# circuit.net
KiCad netlist of a schematic drawn in EAGLE
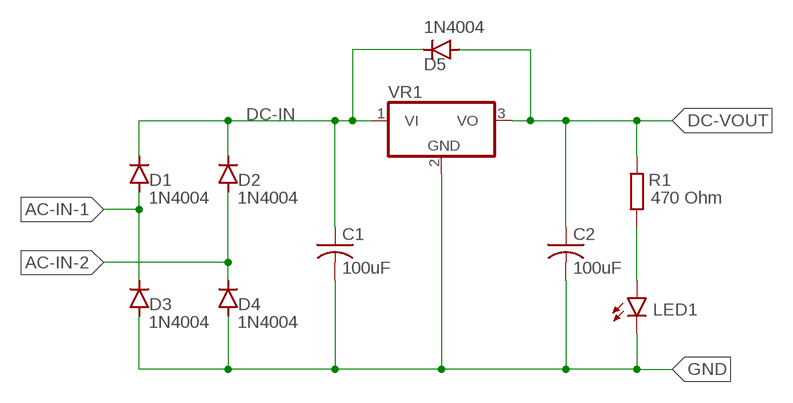
[diagram p0: schematic, sheet 1]

(export (version "E")
  (design (tool "Eeschema 10.0.6"))
  (components
    (comp (ref "C1")
      (value "100uF")
      (footprint "eagle-import:C050-045X075")
      (libsource (lib "eagle-import") (part "C-US050-045X075"))
    )
    (comp (ref "C2")
      (value "100uF")
      (footprint "eagle-import:C050-045X075")
      (libsource (lib "eagle-import") (part "C-US050-045X075"))
    )
    (comp (ref "D1")
      (value "1N4004")
      (footprint "eagle-import:DO41-10")
      (libsource (lib "eagle-import") (part "1N4004"))
    )
    (comp (ref "D2")
      (value "1N4004")
      (footprint "eagle-import:DO41-10")
      (libsource (lib "eagle-import") (part "1N4004"))
    )
    (comp (ref "D3")
      (value "1N4004")
      (footprint "eagle-import:DO41-10")
      (libsource (lib "eagle-import") (part "1N4004"))
    )
    (comp (ref "D4")
      (value "1N4004")
      (footprint "eagle-import:DO41-10")
      (libsource (lib "eagle-import") (part "1N4004"))
    )
    (comp (ref "D5")
      (value "1N4004")
      (footprint "eagle-import:DO41-10")
      (libsource (lib "eagle-import") (part "1N4004"))
    )
    (comp (ref "LED1")
      (value "LED5MM")
      (footprint "eagle-import:LED5MM")
      (libsource (lib "eagle-import") (part "LED5MM"))
    )
    (comp (ref "R1")
      (value "470 Ohm")
      (footprint "eagle-import:0207_10")
      (libsource (lib "eagle-import") (part "R-EU_0207/10"))
    )
    (comp (ref "VR1")
      (value "788TV")
      (footprint "eagle-import:TO220V")
      (libsource (lib "eagle-import") (part "78TV8"))
    )
  )
  (nets
    (net (code "1") (name "/DC-IN") (class "Default")
      (node (ref "C1") (pin "1") (pinfunction "1_1") (pintype "passive"))
      (node (ref "D1") (pin "C") (pinfunction "C_C") (pintype "passive"))
      (node (ref "D2") (pin "C") (pinfunction "C_C") (pintype "passive"))
      (node (ref "D5") (pin "C") (pinfunction "C_C") (pintype "passive"))
      (node (ref "VR1") (pin "1") (pinfunction "VI_1") (pintype "input"))
    )
    (net (code "2") (name "AC-IN-1") (class "Default")
      (node (ref "D1") (pin "A") (pinfunction "A_A") (pintype "passive"))
      (node (ref "D3") (pin "C") (pinfunction "C_C") (pintype "passive"))
    )
    (net (code "3") (name "AC-IN-2") (class "Default")
      (node (ref "D2") (pin "A") (pinfunction "A_A") (pintype "passive"))
      (node (ref "D4") (pin "C") (pinfunction "C_C") (pintype "passive"))
    )
    (net (code "4") (name "DC-VOUT") (class "Default")
      (node (ref "C2") (pin "1") (pinfunction "1_1") (pintype "passive"))
      (node (ref "D5") (pin "A") (pinfunction "A_A") (pintype "passive"))
      (node (ref "R1") (pin "2") (pinfunction "2_2") (pintype "passive"))
      (node (ref "VR1") (pin "3") (pinfunction "VO_3") (pintype "passive"))
    )
    (net (code "5") (name "GND") (class "Default")
      (node (ref "C1") (pin "2") (pinfunction "2_2") (pintype "passive"))
      (node (ref "C2") (pin "2") (pinfunction "2_2") (pintype "passive"))
      (node (ref "D3") (pin "A") (pinfunction "A_A") (pintype "passive"))
      (node (ref "D4") (pin "A") (pinfunction "A_A") (pintype "passive"))
      (node (ref "LED1") (pin "K") (pinfunction "C_K") (pintype "passive"))
      (node (ref "VR1") (pin "2") (pinfunction "GND_2") (pintype "passive"))
    )
    (net (code "6") (name "Net-(LED1-PadA)") (class "Default")
      (node (ref "LED1") (pin "A") (pinfunction "A_A") (pintype "passive"))
      (node (ref "R1") (pin "1") (pinfunction "1_1") (pintype "passive"))
    )
  )
)
